# MeArm-v3.net
KiCad netlist of a schematic drawn in EAGLE
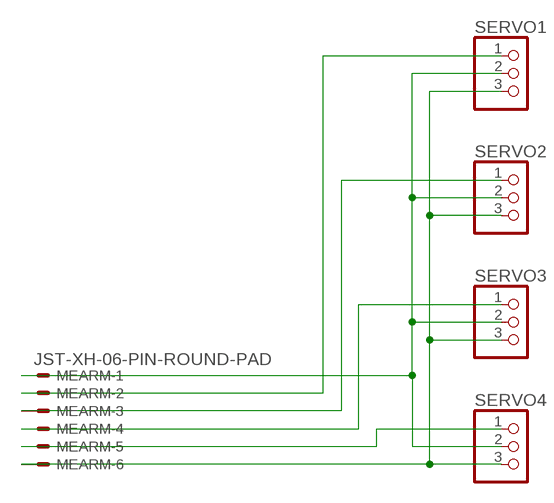
[diagram p0: schematic, sheet 1]

(export (version "E")
  (design (tool "Eeschema 10.0.6"))
  (components
    (comp (ref "MEARM")
      (value "JST-XH-06-PIN-ROUND-PAD")
      (footprint "eagle-import:JST-XH-06-PACKAGE-ROUND-PAD")
      (libsource (lib "eagle-import") (part "JST-XH-06-PIN-ROUND-PAD"))
    )
    (comp (ref "SERVO1")
      (value "PINHD-1X3")
      (footprint "eagle-import:1X03")
      (libsource (lib "eagle-import") (part "PINHD-1X3"))
    )
    (comp (ref "SERVO2")
      (value "PINHD-1X3")
      (footprint "eagle-import:1X03")
      (libsource (lib "eagle-import") (part "PINHD-1X3"))
    )
    (comp (ref "SERVO3")
      (value "PINHD-1X3")
      (footprint "eagle-import:1X03")
      (libsource (lib "eagle-import") (part "PINHD-1X3"))
    )
    (comp (ref "SERVO4")
      (value "PINHD-1X3")
      (footprint "eagle-import:1X03")
      (libsource (lib "eagle-import") (part "PINHD-1X3"))
    )
  )
  (nets
    (net (code "1") (name "Net-(MEARMA-S)") (class "Default")
      (node (ref "MEARM") (pin "1") (pinfunction "S_1") (pintype "passive"))
      (node (ref "SERVO1") (pin "2") (pinfunction "2_2") (pintype "passive"))
      (node (ref "SERVO2") (pin "2") (pinfunction "2_2") (pintype "passive"))
      (node (ref "SERVO3") (pin "2") (pinfunction "2_2") (pintype "passive"))
      (node (ref "SERVO4") (pin "2") (pinfunction "2_2") (pintype "passive"))
    )
    (net (code "2") (name "Net-(MEARMB-S)") (class "Default")
      (node (ref "MEARM") (pin "2") (pinfunction "S_2") (pintype "passive"))
      (node (ref "SERVO1") (pin "1") (pinfunction "1_1") (pintype "passive"))
    )
    (net (code "3") (name "Net-(MEARMC-S)") (class "Default")
      (node (ref "MEARM") (pin "3") (pinfunction "S_3") (pintype "passive"))
      (node (ref "SERVO2") (pin "1") (pinfunction "1_1") (pintype "passive"))
    )
    (net (code "4") (name "Net-(MEARMD-S)") (class "Default")
      (node (ref "MEARM") (pin "4") (pinfunction "S_4") (pintype "passive"))
      (node (ref "SERVO3") (pin "1") (pinfunction "1_1") (pintype "passive"))
    )
    (net (code "5") (name "Net-(MEARME-S)") (class "Default")
      (node (ref "MEARM") (pin "5") (pinfunction "S_5") (pintype "passive"))
      (node (ref "SERVO4") (pin "1") (pinfunction "1_1") (pintype "passive"))
    )
    (net (code "6") (name "Net-(MEARMF-S)") (class "Default")
      (node (ref "MEARM") (pin "6") (pinfunction "S_6") (pintype "passive"))
      (node (ref "SERVO1") (pin "3") (pinfunction "3_3") (pintype "passive"))
      (node (ref "SERVO2") (pin "3") (pinfunction "3_3") (pintype "passive"))
      (node (ref "SERVO3") (pin "3") (pinfunction "3_3") (pintype "passive"))
      (node (ref "SERVO4") (pin "3") (pinfunction "3_3") (pintype "passive"))
    )
  )
)
